# 09_-_EMC-Power.net
KiCad netlist of a schematic drawn in Altium Designer
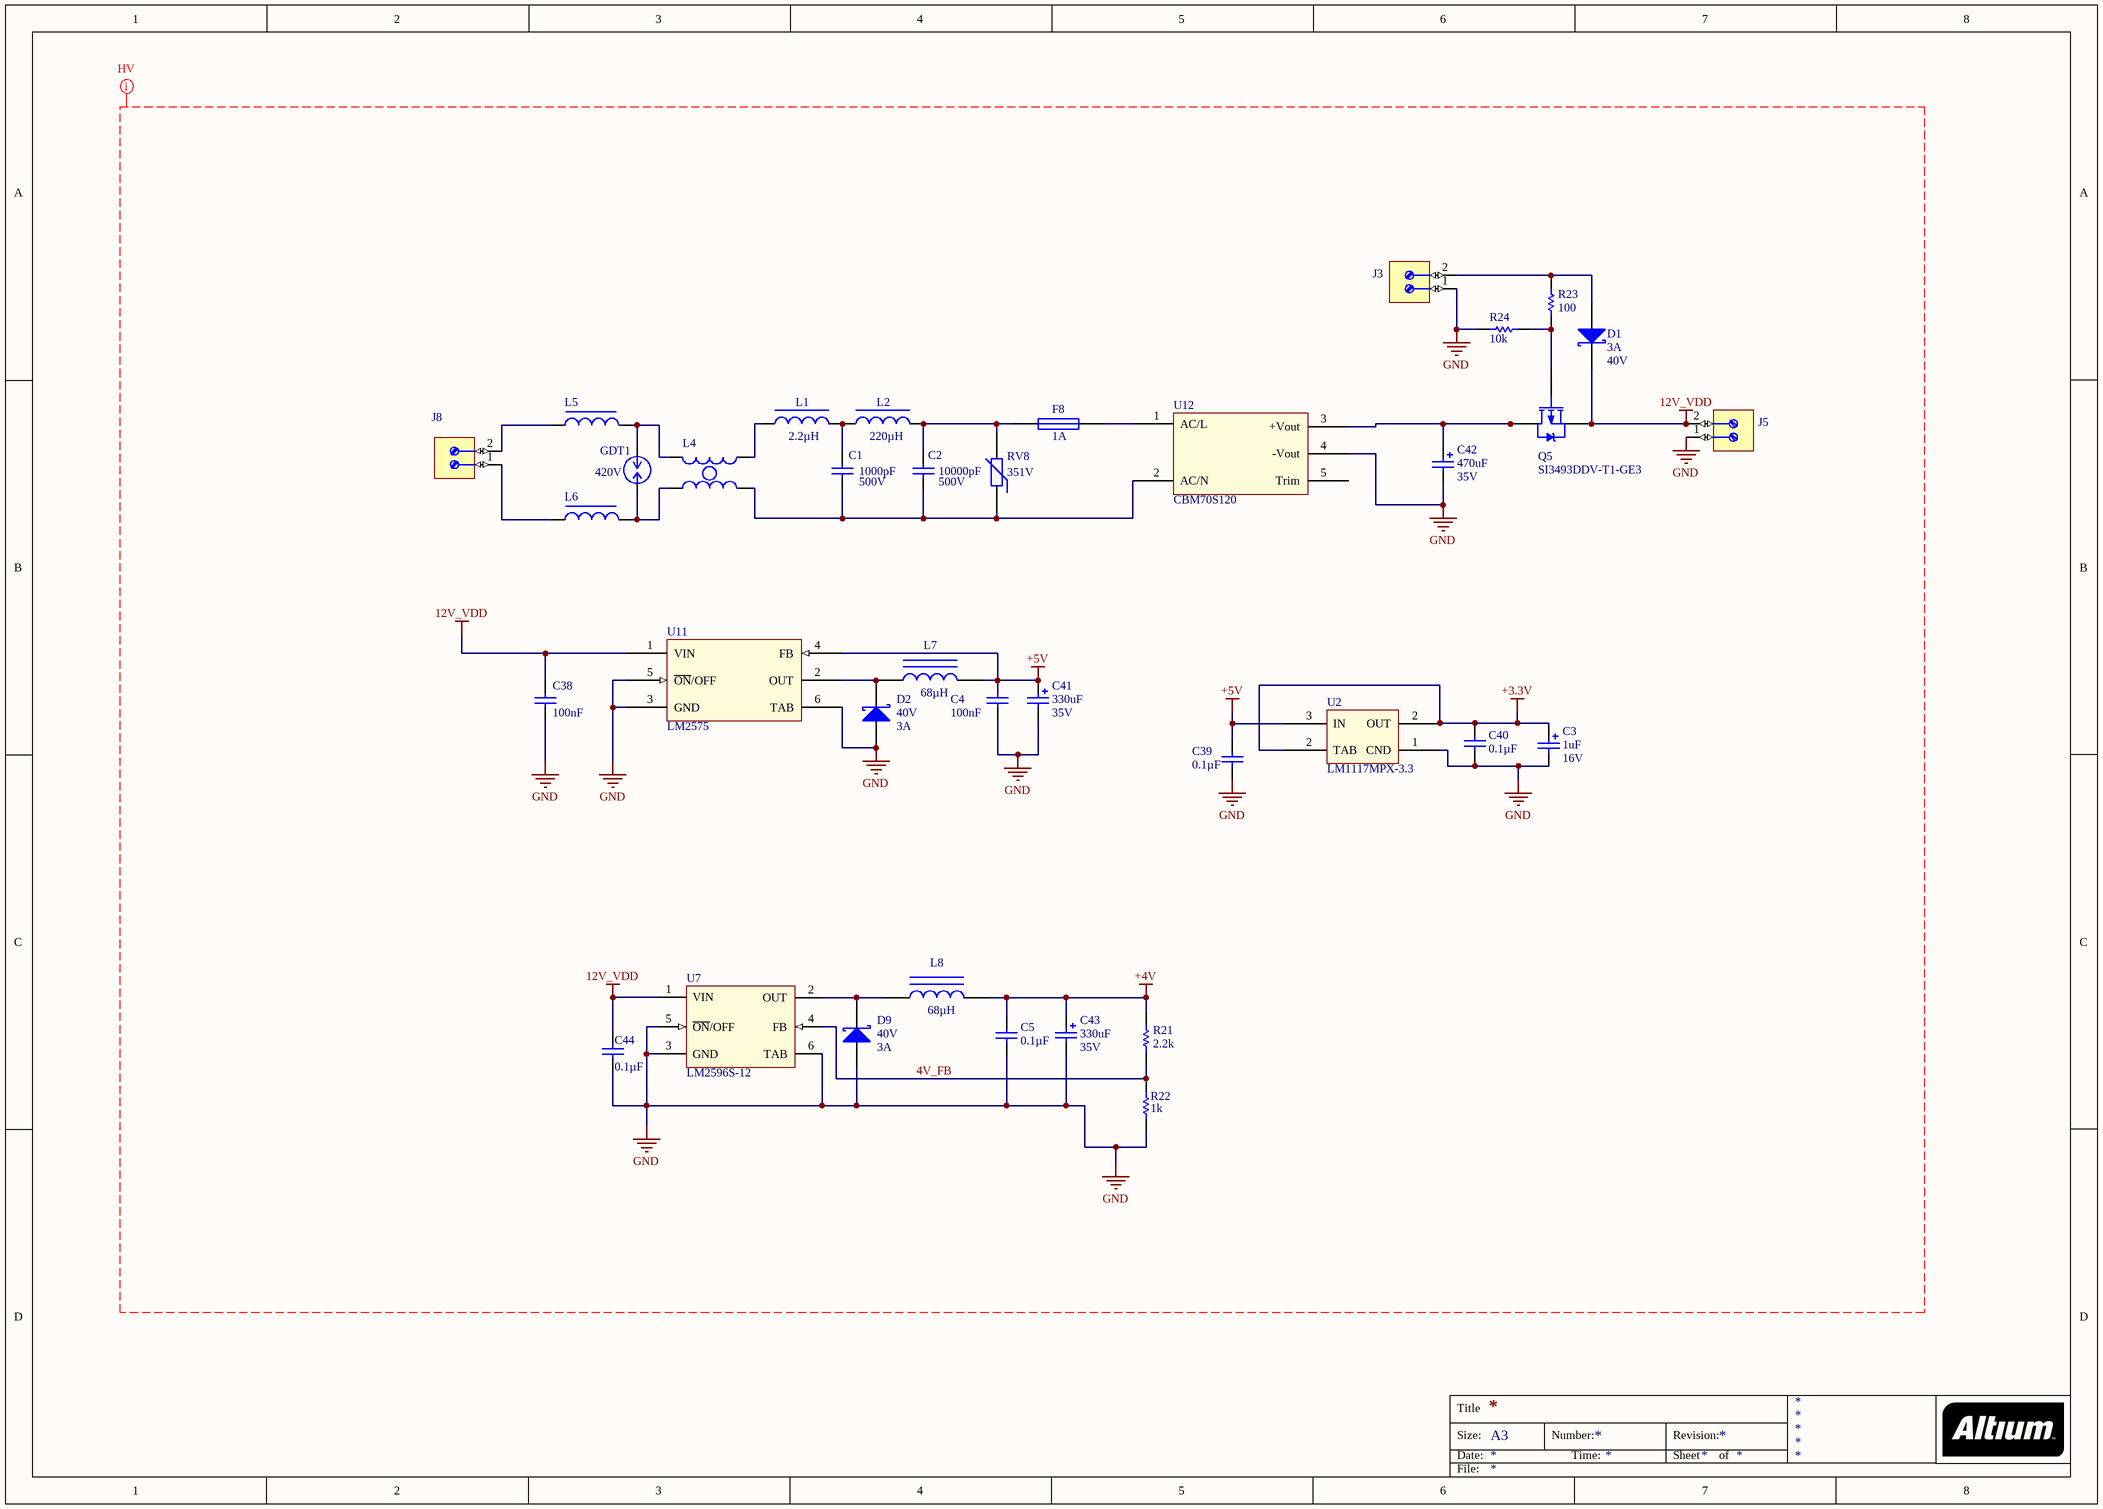
[diagram p0: [09] - EMC-Power.SchDoc]

(export (version "E")
  (design (tool "Eeschema 10.0.6"))
  (components
    (comp (ref "C1")
      (value "Capacitor")
      (footprint "Blue Tractor-2021:CAPASITOR_1206")
      (description "Chip Capacitor Nonpolar")
      (fields
        (field (name "MANUFACTURER") "Samsung Electro-Mechanics America, Inc")
        (field (name "MANUFACTURER PART NUMBER") "CL31B102KGFNFNE")
        (field (name "CAPACITANCE") "1000pF")
        (field (name "VOLTAGE - RATED") "500V")
        (field (name "PUBLISHER") "Altium Limited")
      )
      (libsource (lib "Altium_Library") (part "Capacitor"))
    )
    (comp (ref "C2")
      (value "Capacitor")
      (footprint "Blue Tractor-2021:CAPASITOR_1206")
      (description "Chip Capacitor Nonpolar")
      (fields
        (field (name "MANUFACTURER") "Samsung Electro-Mechanics America, Inc")
        (field (name "MANUFACTURER PART NUMBER") "CL31B103KGFNNNE")
        (field (name "CAPACITANCE") "10000pF")
        (field (name "VOLTAGE - RATED") "500V")
      )
      (libsource (lib "Altium_Library") (part "Capacitor"))
    )
    (comp (ref "C3")
      (value "Capacitor Polarized")
      (footprint "Blue Tractor-2021:Tantalum 3216 A")
      (description "Tantalum Capacitor")
      (fields
        (field (name "MANUFACTURER") "Vishay Sprague")
        (field (name "MANUFACTURER PART NUMBER") "293D105X9016A2TE3")
        (field (name "CAPACITANCE") "1uF")
        (field (name "VOLTAGE RATING") "16V")
      )
      (libsource (lib "Altium_Library") (part "Capacitor Polarized"))
    )
    (comp (ref "C4")
      (value "Capacitor")
      (footprint "Blue Tractor-2021:0603_C")
      (description "Chip Capacitor Nonpolar")
      (fields
        (field (name "MANUFACTURER") "Kemet")
        (field (name "MANUFACTURER PART NUMBER") "C0603C104K5RACTU")
        (field (name "CAPACITANCE") "100nF")
      )
      (libsource (lib "Altium_Library") (part "Capacitor"))
    )
    (comp (ref "C5")
      (value "Capacitor")
      (footprint "Blue Tractor-2021:0603_C")
      (description "Chip Capacitor Nonpolar")
      (fields
        (field (name "MANUFACTURER") "Kemet")
        (field (name "MANUFACTURER PART NUMBER") "C0603C104K5RACTU")
        (field (name "CAPACITANCE") "0.1µF")
      )
      (libsource (lib "Altium_Library") (part "Capacitor"))
    )
    (comp (ref "C38")
      (value "100nF")
      (footprint "Blue Tractor-2021:0603_C")
      (description "Capacitor 0603")
      (fields
        (field (name "MANUFACTURER") "Kemet")
        (field (name "MANUFACTURER PART NUMBER") "C0603C473K5RACTU")
      )
      (libsource (lib "Altium_Library") (part "Capacitor"))
    )
    (comp (ref "C39")
      (value "Capacitor")
      (footprint "Blue Tractor-2021:0603_C")
      (description "Chip Capacitor Nonpolar")
      (fields
        (field (name "MANUFACTURER") "Kemet")
        (field (name "MANUFACTURER PART NUMBER") "C0603C104K5RACTU")
        (field (name "CAPACITANCE") "0.1µF")
      )
      (libsource (lib "Altium_Library") (part "Capacitor"))
    )
    (comp (ref "C40")
      (value "Capacitor")
      (footprint "Blue Tractor-2021:0603_C")
      (description "Chip Capacitor Nonpolar")
      (fields
        (field (name "MANUFACTURER") "Kemet")
        (field (name "MANUFACTURER PART NUMBER") "C0603C104K5RACTU")
        (field (name "CAPACITANCE") "0.1µF")
      )
      (libsource (lib "Altium_Library") (part "Capacitor"))
    )
    (comp (ref "C41")
      (value "Capacitor Polarized")
      (footprint "Blue Tractor-2021:Aluminium SMD G")
      (description "Aluminium SMD Capacitors")
      (fields
        (field (name "MANUFACTURER") "Panasonic")
        (field (name "MANUFACTURER PART NUMBER") "EEE-1VA331P")
        (field (name "CAPACITANCE") "330uF")
        (field (name "VOLTAGE") "35V")
      )
      (libsource (lib "Altium_Library") (part "Capacitor Polarized"))
    )
    (comp (ref "C42")
      (value "Capacitor Polarized")
      (footprint "Aluminium SMD G")
      (description "Aluminium SMD Capacitors")
      (fields
        (field (name "MANUFACTURER") "Nichicon")
        (field (name "MANUFACTURER PART NUMBER") "UCL1V471MNL1GS")
        (field (name "CAPACITANCE") "470uF")
        (field (name "VOLTAGE RATING") "35V")
      )
      (libsource (lib "Altium_Library") (part "Capacitor Polarized"))
    )
    (comp (ref "C43")
      (value "Capacitor Polarized")
      (footprint "Blue Tractor-2021:Aluminium SMD G")
      (description "Aluminium SMD Capacitors")
      (fields
        (field (name "MANUFACTURER") "Panasonic")
        (field (name "MANUFACTURER PART NUMBER") "EEE-1VA331P")
        (field (name "CAPACITANCE") "330uF")
        (field (name "VOLTAGE") "35V")
      )
      (libsource (lib "Altium_Library") (part "Capacitor Polarized"))
    )
    (comp (ref "C44")
      (value "Capacitor")
      (footprint "Blue Tractor-2021:0603_C")
      (description "Chip Capacitor Nonpolar")
      (fields
        (field (name "MANUFACTURER") "Kemet")
        (field (name "MANUFACTURER PART NUMBER") "C0603C104K5RACTU")
        (field (name "CAPACITANCE") "0.1µF")
      )
      (libsource (lib "Altium_Library") (part "Capacitor"))
    )
    (comp (ref "D1")
      (value "SK32")
      (footprint "Blue Tractor-2021:D-Schottky")
      (description "Schottky Rectifier")
      (fields
        (field (name "MANUFACTURER") "Diodes")
        (field (name "MANUFACTURER PART NUMBER") "B340A-13-F")
        (field (name "OUTPUT CURRENT") "3A")
        (field (name "VOLTAGE") "40V")
      )
      (libsource (lib "GSMInformer-PB-TC.v1.0-2013") (part "SK32"))
    )
    (comp (ref "D2")
      (value "SK32")
      (footprint "Blue Tractor-2021:D-Schottky")
      (description "Schottky Rectifier")
      (fields
        (field (name "MANUFACTURER") "Diodes")
        (field (name "MANUFACTURER PART NUMBER") "B340A-13-F")
        (field (name "OUTPUT CURRENT") "3A")
        (field (name "VOLTAGE") "40V")
      )
      (libsource (lib "GSMInformer-PB-TC.v1.0-2013") (part "SK32"))
    )
    (comp (ref "D9")
      (value "SK32")
      (footprint "Blue Tractor-2021:D-Schottky")
      (description "Schottky Rectifier")
      (fields
        (field (name "MANUFACTURER") "Diodes")
        (field (name "MANUFACTURER PART NUMBER") "B340A-13-F")
        (field (name "OUTPUT CURRENT") "3A")
        (field (name "VOLTAGE") "40V")
      )
      (libsource (lib "GSMInformer-PB-TC.v1.0-2013") (part "SK32"))
    )
    (comp (ref "F8")
      (value "1A")
      (footprint "Blue Tractor-2021:FUSR_LITTELFUSE_2920L")
      (description "Fuse")
      (fields
        (field (name "MANUFACTURER") "TE Connectivity Raychem Circuit Protection")
        (field (name "MANUFACTURER PART NUMBER") "LVR100S")
      )
      (libsource (lib "Altium_Library") (part "Fuse"))
    )
    (comp (ref "GDT1")
      (value "Gas Discharge Tube")
      (footprint "Blue Tractor-2021:GTCA28_TYCO_TYC")
      (fields
        (field (name "MANUFACTURER") "TE Connectivity Raychem Circuit Protection")
        (field (name "MANUFACTURER PART NUMBER") "GTCA28-421M-R05")
        (field (name "TOLERANCE") "±20%")
        (field (name "VOLTAGE - DC SPARK OVER (NOM)") "420V")
      )
      (libsource (lib "Blue Tractor-2021") (part "Gas Discharge Tube"))
    )
    (comp (ref "J3")
      (value "~")
      (footprint "Blue Tractor-2021:Connector -PHOENIX_1715721")
      (description "Terminal Block, 2 Positions, Screw Connection")
      (fields
        (field (name "PART NUMBER") "PHOENIX_1715721")
        (field (name "MANUFACTURER") "PHOENIX CONTACT")
        (field (name "AUTHOR") "CERN DEM JLC")
      )
      (libsource (lib "Connectors") (part "Terminal Block_2 Positions_Screw Connection"))
    )
    (comp (ref "J5")
      (value "~")
      (footprint "Blue Tractor-2021:Connector -PHOENIX_1715721")
      (description "Terminal Block, 2 Positions, Screw Connection")
      (fields
        (field (name "PART NUMBER") "PHOENIX_1715721")
        (field (name "MANUFACTURER") "PHOENIX CONTACT")
        (field (name "AUTHOR") "CERN DEM JLC")
      )
      (libsource (lib "") (part "Terminal Block_2 Positions_Screw Connection_1"))
    )
    (comp (ref "J8")
      (value "~")
      (footprint "Blue Tractor-2021:Connector -PHOENIX_1715721")
      (description "Terminal Block, 2 Positions, Screw Connection")
      (fields
        (field (name "PART NUMBER") "PHOENIX_1715721")
        (field (name "MANUFACTURER") "PHOENIX CONTACT")
        (field (name "AUTHOR") "CERN DEM JLC")
      )
      (libsource (lib "Connectors") (part "Terminal Block_2 Positions_Screw Connection"))
    )
    (comp (ref "L1")
      (value "Inductor")
      (footprint "Blue Tractor-2021:? INDUCTOR_TDK")
      (description "Inductors throgh hole")
      (fields
        (field (name "MANUFACTURER") "TDK Corporation")
        (field (name "MANUFACTURER PART NUMBER") "VLS252012T-2R2M1R3")
        (field (name "INDUCTANCE") "2.2µH")
      )
      (libsource (lib "Altium_Library") (part "InductorCore"))
    )
    (comp (ref "L2")
      (value "Inductor")
      (footprint "Blue Tractor-2021:L8 -INDUCTOR_BOURNS_SRR1260")
      (description "Inductors throgh hole")
      (fields
        (field (name "MANUFACTURER") "Bourns Inc.")
        (field (name "MANUFACTURER PART NUMBER") "SRR1260-221K")
        (field (name "INDUCTANCE") "220µH")
      )
      (libsource (lib "Altium_Library") (part "InductorCore"))
    )
    (comp (ref "L4")
      (value "RN114-1-02 Current-compensated Chokes")
      (footprint "Blue Tractor-2021:IND: RN152")
      (fields
        (field (name "MANUFACTURER") "Schaffner EMC Inc")
        (field (name "MANUFACTURER PART NUMBER") "RN114-1-02")
      )
      (libsource (lib "Blue Tractor-2021") (part "RN114-1-02 Current-compensated Chokes"))
    )
    (comp (ref "L5")
      (value "Inductor_BFB20022-4B-RC-ND")
      (footprint "Blue Tractor-2021:INDUCTOR FB20022")
      (description "BFB20022-4B-RC-ND")
      (libsource (lib "Blue Tractor-2021") (part "Inductor_BFB20022-4B-RC-ND"))
    )
    (comp (ref "L6")
      (value "Inductor_BFB20022-4B-RC-ND")
      (footprint "Blue Tractor-2021:INDUCTOR FB20022")
      (description "BFB20022-4B-RC-ND")
      (libsource (lib "Blue Tractor-2021") (part "Inductor_BFB20022-4B-RC-ND"))
    )
    (comp (ref "L7")
      (value "SRR1210")
      (footprint "Blue Tractor-2021:L8 -INDUCTOR_BOURNS_SRR1260")
      (description "Magnetic-Core Inductor")
      (fields
        (field (name "MANUFACTURER") "Bourns Inc.")
        (field (name "MANUFACTURER PART NUMBER") "SRR1210-680M")
        (field (name "INDUCTANCE") "68µH")
        (field (name "PUBLISHER") "Altium Limited")
      )
      (libsource (lib "GSMInformer-PB-TC.v1.0-2013") (part "SRR1210"))
    )
    (comp (ref "L8")
      (value "SRR1210")
      (footprint "Blue Tractor-2021:L8 -INDUCTOR_BOURNS_SRR1260")
      (description "Magnetic-Core Inductor")
      (fields
        (field (name "MANUFACTURER") "Bourns Inc.")
        (field (name "MANUFACTURER PART NUMBER") "SRR1210-680M")
        (field (name "INDUCTANCE") "68µH")
        (field (name "PUBLISHER") "Altium Limited")
      )
      (libsource (lib "GSMInformer-PB-TC.v1.0-2013") (part "SRR1210"))
    )
    (comp (ref "Q5")
      (value "PMOSFET")
      (footprint "SOT23-6")
      (description "MOSFET P-CHANNEL 20V 8A 6TSOP")
      (fields
        (field (name "MANUFACTURER") "Vishay")
        (field (name "MANUFACTURER PART NUMBER") "SI3493DDV-T1-GE3")
      )
      (libsource (lib "BaseNode v1.2") (part "PMOSFET"))
    )
    (comp (ref "R21")
      (value "Res1")
      (footprint "Blue Tractor-2021:0603_R")
      (description "Chip Resistor")
      (fields
        (field (name "MANUFACTURER") "Panasonic")
        (field (name "MANUFACTURER PART NUMBER") "ERJ-3GEYJ222V")
        (field (name "RESISTANCE") "2.2k")
      )
      (libsource (lib "Altium_Library") (part "Res1"))
    )
    (comp (ref "R22")
      (value "Res1")
      (footprint "Blue Tractor-2021:0603_R")
      (description "Chip Resistor")
      (fields
        (field (name "MANUFACTURER") "Panasonic")
        (field (name "MANUFACTURER PART NUMBER") "ERJ-3GEYJ102V")
        (field (name "RESISTANCE") "1k")
      )
      (libsource (lib "Altium_Library") (part "Res1"))
    )
    (comp (ref "R23")
      (value "Res1")
      (footprint "Blue Tractor-2021:0603_R")
      (description "Chip Resistor")
      (fields
        (field (name "MANUFACTURER") "Panasonic")
        (field (name "MANUFACTURER PART NUMBER") "ERJ-3GEYJ222V")
        (field (name "RESISTANCE") "100")
      )
      (libsource (lib "Altium_Library") (part "Res1"))
    )
    (comp (ref "R24")
      (value "Res1")
      (footprint "Blue Tractor-2021:0603_R")
      (description "Chip Resistor")
      (fields
        (field (name "MANUFACTURER") "Panasonic")
        (field (name "MANUFACTURER PART NUMBER") "ERJ-3GEYJ222V")
        (field (name "RESISTANCE") "10k")
      )
      (libsource (lib "Altium_Library") (part "Res1"))
    )
    (comp (ref "RV8")
      (value "Res Varistor")
      (footprint "S14K250:VARS_B72214S0271K101_TDK")
      (fields
        (field (name "MANUFACTURER") "EPCOS Inc")
        (field (name "MANUFACTURER PART NUMBER") "S14K250")
        (field (name "VARISTOR VOLTAGE (MIN)") "351V")
        (field (name "PUBLISHER") "Altium Limited")
      )
      (libsource (lib "Altium_Library") (part "Res Varistor"))
    )
    (comp (ref "U2")
      (value "LM1117MPX-3.3")
      (footprint "Blue Tractor-2021:LM1117IMPX-3.3")
      (libsource (lib "Blue Tractor-2021") (part "LM1117MPX-3.3"))
    )
    (comp (ref "U7")
      (value "LM2596S-12")
      (footprint "TO-263-5")
      (libsource (lib "Blue Tractor-2021") (part "LM2596S-12"))
    )
    (comp (ref "U11")
      (value "LM2575")
      (footprint "Blue Tractor-2021:TO-263-5")
      (libsource (lib "Blue Tractor-2021") (part "LM2575"))
    )
    (comp (ref "U12")
      (value "CBM70S120")
      (footprint "Blue Tractor-2021:MOD: CBM70S")
      (description "AC-DC ~230-12")
      (libsource (lib "Blue Tractor-2021") (part "CBM70S120"))
    )
  )
  (nets
    (net (code "1") (name "+3.3V") (class "Default")
      (node (ref "C3") (pin "1") (pinfunction "1_1") (pintype "passive"))
      (node (ref "C40") (pin "2") (pinfunction "2_2") (pintype "passive"))
      (node (ref "U2") (pin "2") (pinfunction "TAB_2") (pintype "power_in"))
    )
    (net (code "2") (name "+4V") (class "Default")
      (node (ref "C43") (pin "1") (pinfunction "1_1") (pintype "passive"))
      (node (ref "C5") (pin "2") (pinfunction "2_2") (pintype "passive"))
      (node (ref "L8") (pin "2") (pinfunction "2_2") (pintype "passive"))
      (node (ref "R21") (pin "1") (pinfunction "1_1") (pintype "passive"))
    )
    (net (code "3") (name "+5V") (class "Default")
      (node (ref "C39") (pin "2") (pinfunction "2_2") (pintype "passive"))
      (node (ref "C4") (pin "2") (pinfunction "2_2") (pintype "passive"))
      (node (ref "C41") (pin "1") (pinfunction "1_1") (pintype "passive"))
      (node (ref "L7") (pin "2") (pinfunction "2_2") (pintype "passive"))
      (node (ref "U11") (pin "4") (pinfunction "FB_4") (pintype "input"))
      (node (ref "U2") (pin "3") (pinfunction "IN_3") (pintype "power_in"))
    )
    (net (code "4") (name "/4V_FB") (class "Default")
      (node (ref "R21") (pin "2") (pinfunction "2_2") (pintype "passive"))
      (node (ref "R22") (pin "2") (pinfunction "2_2") (pintype "passive"))
      (node (ref "U7") (pin "4") (pinfunction "FB_4") (pintype "input"))
    )
    (net (code "5") (name "12V_VDD") (class "Default")
      (node (ref "C38") (pin "2") (pinfunction "2_2") (pintype "passive"))
      (node (ref "C44") (pin "2") (pinfunction "2_2") (pintype "passive"))
      (node (ref "D1") (pin "2") (pinfunction "K_2") (pintype "passive"))
      (node (ref "J5") (pin "2") (pinfunction "2_2") (pintype "bidirectional"))
      (node (ref "Q5") (pin "4") (pinfunction "S_4") (pintype "passive"))
      (node (ref "U11") (pin "1") (pinfunction "VIN_1") (pintype "power_in"))
      (node (ref "U7") (pin "1") (pinfunction "VIN_1") (pintype "power_in"))
    )
    (net (code "6") (name "GND") (class "Default")
      (node (ref "C3") (pin "2") (pinfunction "2_2") (pintype "passive"))
      (node (ref "C38") (pin "1") (pinfunction "1_1") (pintype "passive"))
      (node (ref "C39") (pin "1") (pinfunction "1_1") (pintype "passive"))
      (node (ref "C4") (pin "1") (pinfunction "1_1") (pintype "passive"))
      (node (ref "C40") (pin "1") (pinfunction "1_1") (pintype "passive"))
      (node (ref "C41") (pin "2") (pinfunction "2_2") (pintype "passive"))
      (node (ref "C42") (pin "2") (pinfunction "2_2") (pintype "passive"))
      (node (ref "C43") (pin "2") (pinfunction "2_2") (pintype "passive"))
      (node (ref "C44") (pin "1") (pinfunction "1_1") (pintype "passive"))
      (node (ref "C5") (pin "1") (pinfunction "1_1") (pintype "passive"))
      (node (ref "D2") (pin "1") (pinfunction "A_1") (pintype "passive"))
      (node (ref "D9") (pin "1") (pinfunction "A_1") (pintype "passive"))
      (node (ref "J3") (pin "1") (pinfunction "1_1") (pintype "bidirectional"))
      (node (ref "J5") (pin "1") (pinfunction "1_1") (pintype "bidirectional"))
      (node (ref "R22") (pin "1") (pinfunction "1_1") (pintype "passive"))
      (node (ref "R24") (pin "2") (pinfunction "2_2") (pintype "passive"))
      (node (ref "U11") (pin "3") (pinfunction "GND_3") (pintype "power_in"))
      (node (ref "U11") (pin "5") (pinfunction "~{ON}/OFF_5") (pintype "input"))
      (node (ref "U11") (pin "6") (pinfunction "TAB_6") (pintype "power_in"))
      (node (ref "U12") (pin "4") (pinfunction "-Vout_4") (pintype "power_in"))
      (node (ref "U2") (pin "1") (pinfunction "CND_1") (pintype "power_in"))
      (node (ref "U7") (pin "3") (pinfunction "GND_3") (pintype "power_in"))
      (node (ref "U7") (pin "5") (pinfunction "~{ON}/OFF_5") (pintype "input"))
      (node (ref "U7") (pin "6") (pinfunction "TAB_6") (pintype "power_in"))
    )
    (net (code "7") (name "Net-(C1-Pad2)") (class "Default")
      (node (ref "C1") (pin "2") (pinfunction "2_2") (pintype "passive"))
      (node (ref "L1") (pin "2") (pinfunction "2_2") (pintype "passive"))
      (node (ref "L2") (pin "1") (pinfunction "1_1") (pintype "passive"))
    )
    (net (code "8") (name "Net-(C2-Pad2)") (class "Default")
      (node (ref "C2") (pin "2") (pinfunction "2_2") (pintype "passive"))
      (node (ref "F8") (pin "1") (pinfunction "1_1") (pintype "passive"))
      (node (ref "L2") (pin "2") (pinfunction "2_2") (pintype "passive"))
      (node (ref "RV8") (pin "2") (pinfunction "2_2") (pintype "passive"))
    )
    (net (code "9") (name "Net-(D1-A)") (class "Default")
      (node (ref "D1") (pin "1") (pinfunction "A_1") (pintype "passive"))
      (node (ref "J3") (pin "2") (pinfunction "2_2") (pintype "bidirectional"))
      (node (ref "R23") (pin "1") (pinfunction "1_1") (pintype "passive"))
    )
    (net (code "10") (name "Net-(D2-K)") (class "Default")
      (node (ref "D2") (pin "2") (pinfunction "K_2") (pintype "passive"))
      (node (ref "L7") (pin "1") (pinfunction "1_1") (pintype "passive"))
      (node (ref "U11") (pin "2") (pinfunction "OUT_2") (pintype "power_in"))
    )
    (net (code "11") (name "Net-(D9-K)") (class "Default")
      (node (ref "D9") (pin "2") (pinfunction "K_2") (pintype "passive"))
      (node (ref "L8") (pin "1") (pinfunction "1_1") (pintype "passive"))
      (node (ref "U7") (pin "2") (pinfunction "OUT_2") (pintype "power_in"))
    )
    (net (code "12") (name "Net-(GDT1-Pad1)") (class "Default")
      (node (ref "GDT1") (pin "1") (pinfunction "1_1") (pintype "passive"))
      (node (ref "L4") (pin "3") (pinfunction "3_3") (pintype "passive"))
      (node (ref "L5") (pin "2") (pinfunction "2_2") (pintype "passive"))
    )
    (net (code "13") (name "Net-(GDT1-Pad2)") (class "Default")
      (node (ref "GDT1") (pin "2") (pinfunction "2_2") (pintype "passive"))
      (node (ref "L4") (pin "1") (pinfunction "1_1") (pintype "passive"))
      (node (ref "L6") (pin "2") (pinfunction "2_2") (pintype "passive"))
    )
    (net (code "14") (name "Net-(J8-Pad1)") (class "Default")
      (node (ref "J8") (pin "1") (pinfunction "1_1") (pintype "bidirectional"))
      (node (ref "L6") (pin "1") (pinfunction "1_1") (pintype "passive"))
    )
    (net (code "15") (name "Net-(J8-Pad2)") (class "Default")
      (node (ref "J8") (pin "2") (pinfunction "2_2") (pintype "bidirectional"))
      (node (ref "L5") (pin "1") (pinfunction "1_1") (pintype "passive"))
    )
    (net (code "16") (name "Net-(L1-Pad1)") (class "Default")
      (node (ref "L1") (pin "1") (pinfunction "1_1") (pintype "passive"))
      (node (ref "L4") (pin "4") (pinfunction "4_4") (pintype "passive"))
    )
    (net (code "17") (name "Net-(Q5-G)") (class "Default")
      (node (ref "Q5") (pin "3") (pinfunction "G_3") (pintype "passive"))
      (node (ref "R23") (pin "2") (pinfunction "2_2") (pintype "passive"))
      (node (ref "R24") (pin "1") (pinfunction "1_1") (pintype "passive"))
    )
    (net (code "18") (name "Net-(U12-+Vout)") (class "Default")
      (node (ref "C42") (pin "1") (pinfunction "1_1") (pintype "passive"))
      (node (ref "Q5") (pin "1") (pinfunction "D_1") (pintype "passive"))
      (node (ref "Q5") (pin "2") (pinfunction "D_2") (pintype "passive"))
      (node (ref "Q5") (pin "5") (pinfunction "D_5") (pintype "passive"))
      (node (ref "Q5") (pin "6") (pinfunction "D_6") (pintype "passive"))
      (node (ref "U12") (pin "3") (pinfunction "+Vout_3") (pintype "power_in"))
    )
    (net (code "19") (name "Net-(U12-AC{slash}L)") (class "Default")
      (node (ref "F8") (pin "2") (pinfunction "2_2") (pintype "passive"))
      (node (ref "U12") (pin "1") (pinfunction "AC/L_1") (pintype "power_in"))
    )
    (net (code "20") (name "Net-(U12-AC{slash}N)") (class "Default")
      (node (ref "C1") (pin "1") (pinfunction "1_1") (pintype "passive"))
      (node (ref "C2") (pin "1") (pinfunction "1_1") (pintype "passive"))
      (node (ref "L4") (pin "2") (pinfunction "2_2") (pintype "passive"))
      (node (ref "RV8") (pin "1") (pinfunction "1_1") (pintype "passive"))
      (node (ref "U12") (pin "2") (pinfunction "AC/N_2") (pintype "power_in"))
    )
    (net (code "21") (name "unconnected-(U12-Trim-Pad5)") (class "Default")
      (node (ref "U12") (pin "5") (pinfunction "Trim_5") (pintype "passive"))
    )
  )
)
